# design.net
KiCad netlist of a schematic drawn in Altium Designer
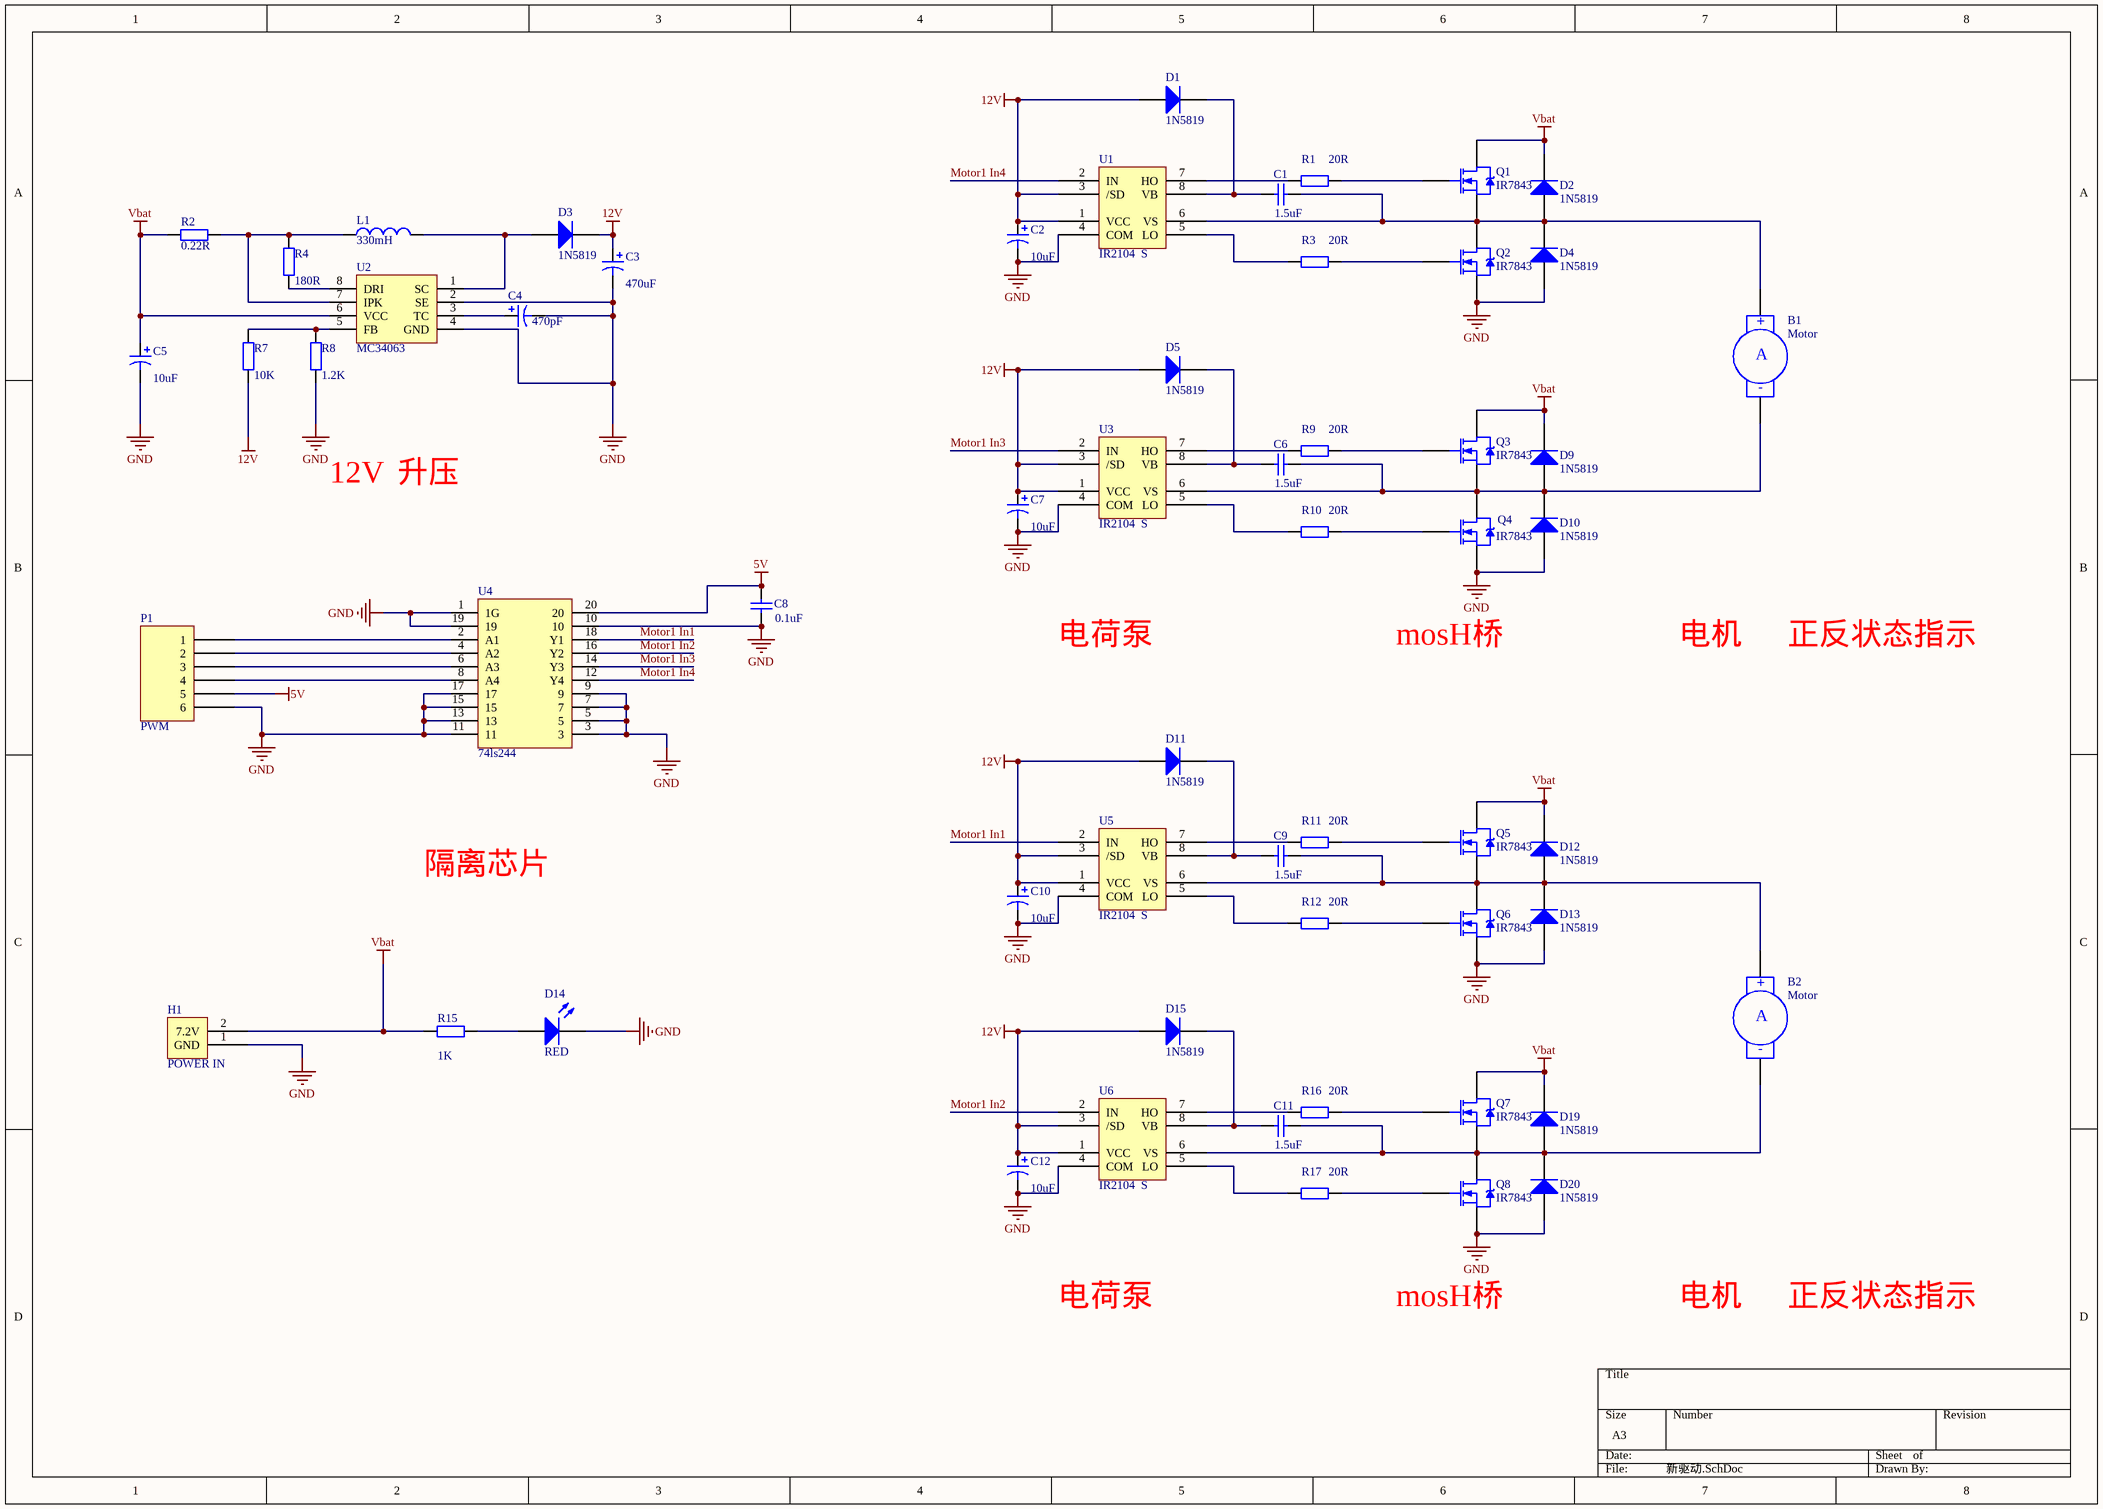
[diagram p0: 新驱动.SchDoc]

(export (version "E")
  (design (tool "Eeschema 10.0.6"))
  (components
    (comp (ref "B1")
      (value "Motor")
      (footprint "KF301-2P")
      (description "Servo Motor")
      (fields (field (name "PUBLISHER") "Altium Limited"))
      (libsource (lib "Miscellaneous Devices") (part "Motor Servo"))
    )
    (comp (ref "B2")
      (value "Motor")
      (footprint "KF301-2P")
      (description "Servo Motor")
      (fields (field (name "PUBLISHER") "Altium Limited"))
      (libsource (lib "Miscellaneous Devices") (part "Motor Servo"))
    )
    (comp (ref "C1")
      (value "1.5uF")
      (footprint "0805(2012)")
      (description "Capacitor")
      (fields (field (name "Comment") "Cap") (field (name "PUBLISHER") "Altium Limited"))
      (libsource (lib "Miscellaneous Devices") (part "Cap"))
    )
    (comp (ref "C2")
      (value "10uF")
      (footprint "SOD-323(0805)")
      (description "Polarized Capacitor (Radial)")
      (fields (field (name "Comment") "Cap Pol1") (field (name "PUBLISHER") "Altium Limited"))
      (libsource (lib "Miscellaneous Devices") (part "Cap Pol1"))
    )
    (comp (ref "C3")
      (value "470uF")
      (footprint "RB5-10.5")
      (description "Polarized Capacitor (Radial)")
      (fields (field (name "Comment") "Cap Pol1") (field (name "PUBLISHER") "Altium Limited"))
      (libsource (lib "Miscellaneous Devices") (part "Cap Pol1"))
    )
    (comp (ref "C4")
      (value "470pF")
      (footprint "SOD-323(0805)")
      (description "Polarized Capacitor (Radial)")
      (fields (field (name "Comment") "Cap Pol1") (field (name "PUBLISHER") "Altium Limited"))
      (libsource (lib "Miscellaneous Devices") (part "Cap Pol1"))
    )
    (comp (ref "C5")
      (value "10uF")
      (footprint "SOD-323(0805)")
      (description "Polarized Capacitor (Radial)")
      (fields (field (name "Comment") "Cap Pol1") (field (name "PUBLISHER") "Altium Limited"))
      (libsource (lib "Miscellaneous Devices") (part "Cap Pol1"))
    )
    (comp (ref "C6")
      (value "1.5uF")
      (footprint "0805(2012)")
      (description "Capacitor")
      (fields (field (name "Comment") "Cap") (field (name "PUBLISHER") "Altium Limited"))
      (libsource (lib "Miscellaneous Devices") (part "Cap"))
    )
    (comp (ref "C7")
      (value "10uF")
      (footprint "SOD-323(0805)")
      (description "Polarized Capacitor (Radial)")
      (fields (field (name "Comment") "Cap Pol1") (field (name "PUBLISHER") "Altium Limited"))
      (libsource (lib "Miscellaneous Devices") (part "Cap Pol1"))
    )
    (comp (ref "C8")
      (value "0.1uF")
      (footprint "0805(2012)")
      (description "Capacitor")
      (fields (field (name "Comment") "Cap") (field (name "PUBLISHER") "Altium Limited"))
      (libsource (lib "Miscellaneous Devices") (part "Cap"))
    )
    (comp (ref "C9")
      (value "1.5uF")
      (footprint "0805(2012)")
      (description "Capacitor")
      (fields (field (name "Comment") "Cap") (field (name "PUBLISHER") "Altium Limited"))
      (libsource (lib "Miscellaneous Devices") (part "Cap"))
    )
    (comp (ref "C10")
      (value "10uF")
      (footprint "SOD-323(0805)")
      (description "Polarized Capacitor (Radial)")
      (fields (field (name "Comment") "Cap Pol1") (field (name "PUBLISHER") "Altium Limited"))
      (libsource (lib "Miscellaneous Devices") (part "Cap Pol1"))
    )
    (comp (ref "C11")
      (value "1.5uF")
      (footprint "0805(2012)")
      (description "Capacitor")
      (fields (field (name "Comment") "Cap") (field (name "PUBLISHER") "Altium Limited"))
      (libsource (lib "Miscellaneous Devices") (part "Cap"))
    )
    (comp (ref "C12")
      (value "10uF")
      (footprint "SOD-323(0805)")
      (description "Polarized Capacitor (Radial)")
      (fields (field (name "Comment") "Cap Pol1") (field (name "PUBLISHER") "Altium Limited"))
      (libsource (lib "Miscellaneous Devices") (part "Cap Pol1"))
    )
    (comp (ref "D1")
      (value "1N5819")
      (footprint "0805(2012)")
      (description "Silicon Epitaxial Planar Diode for Various Detector, Modulator, Demodulator")
      (fields (field (name "PUBLISHER") "Altium Limited"))
      (libsource (lib "Renesas Diode") (part "1N4148"))
    )
    (comp (ref "D2")
      (value "1N5819")
      (footprint "0805(2012)")
      (description "Silicon Epitaxial Planar Diode for Various Detector, Modulator, Demodulator")
      (fields (field (name "PUBLISHER") "Altium Limited"))
      (libsource (lib "Renesas Diode") (part "1N4148"))
    )
    (comp (ref "D3")
      (value "1N5819")
      (footprint "0805(2012)")
      (description "Silicon Epitaxial Planar Diode for Various Detector, Modulator, Demodulator")
      (fields (field (name "PUBLISHER") "Altium Limited"))
      (libsource (lib "Renesas Diode") (part "1N4148"))
    )
    (comp (ref "D4")
      (value "1N5819")
      (footprint "0805(2012)")
      (description "Silicon Epitaxial Planar Diode for Various Detector, Modulator, Demodulator")
      (fields (field (name "PUBLISHER") "Altium Limited"))
      (libsource (lib "13th_motor") (part "1N4148"))
    )
    (comp (ref "D5")
      (value "1N5819")
      (footprint "0805(2012)")
      (description "Silicon Epitaxial Planar Diode for Various Detector, Modulator, Demodulator")
      (fields (field (name "PUBLISHER") "Altium Limited"))
      (libsource (lib "Renesas Diode") (part "1N4148"))
    )
    (comp (ref "D9")
      (value "1N5819")
      (footprint "0805(2012)")
      (description "Silicon Epitaxial Planar Diode for Various Detector, Modulator, Demodulator")
      (fields (field (name "PUBLISHER") "Altium Limited"))
      (libsource (lib "Renesas Diode") (part "1N4148"))
    )
    (comp (ref "D10")
      (value "1N5819")
      (footprint "0805(2012)")
      (description "Silicon Epitaxial Planar Diode for Various Detector, Modulator, Demodulator")
      (fields (field (name "PUBLISHER") "Altium Limited"))
      (libsource (lib "Renesas Diode") (part "1N4148"))
    )
    (comp (ref "D11")
      (value "1N5819")
      (footprint "0805(2012)")
      (description "Silicon Epitaxial Planar Diode for Various Detector, Modulator, Demodulator")
      (fields (field (name "PUBLISHER") "Altium Limited"))
      (libsource (lib "Renesas Diode") (part "1N4148"))
    )
    (comp (ref "D12")
      (value "1N5819")
      (footprint "0805(2012)")
      (description "Silicon Epitaxial Planar Diode for Various Detector, Modulator, Demodulator")
      (fields (field (name "PUBLISHER") "Altium Limited"))
      (libsource (lib "Renesas Diode") (part "1N4148"))
    )
    (comp (ref "D13")
      (value "1N5819")
      (footprint "0805(2012)")
      (description "Silicon Epitaxial Planar Diode for Various Detector, Modulator, Demodulator")
      (fields (field (name "PUBLISHER") "Altium Limited"))
      (libsource (lib "Renesas Diode") (part "1N4148"))
    )
    (comp (ref "D14")
      (value "RED")
      (footprint "0805LED")
      (description "Typical RED, GREEN, YELLOW, AMBER GaAs LED")
      (fields (field (name "PUBLISHER") "Altium Limited"))
      (libsource (lib "Miscellaneous Devices") (part "LED2"))
    )
    (comp (ref "D15")
      (value "1N5819")
      (footprint "0805(2012)")
      (description "Silicon Epitaxial Planar Diode for Various Detector, Modulator, Demodulator")
      (fields (field (name "PUBLISHER") "Altium Limited"))
      (libsource (lib "Renesas Diode") (part "1N4148"))
    )
    (comp (ref "D19")
      (value "1N5819")
      (footprint "0805(2012)")
      (description "Silicon Epitaxial Planar Diode for Various Detector, Modulator, Demodulator")
      (fields (field (name "PUBLISHER") "Altium Limited"))
      (libsource (lib "Renesas Diode") (part "1N4148"))
    )
    (comp (ref "D20")
      (value "1N5819")
      (footprint "0805(2012)")
      (description "Silicon Epitaxial Planar Diode for Various Detector, Modulator, Demodulator")
      (fields (field (name "PUBLISHER") "Altium Limited"))
      (libsource (lib "Renesas Diode") (part "1N4148"))
    )
    (comp (ref "H1")
      (value "POWER IN")
      (footprint "KF301-2P")
      (libsource (lib "MOS motor") (part "POWER IN"))
    )
    (comp (ref "L1")
      (value "330mH")
      (footprint "电感10*12")
      (description "Inductor")
      (fields (field (name "PUBLISHER") "Altium Limited"))
      (libsource (lib "Miscellaneous Devices") (part "Inductor"))
    )
    (comp (ref "P1") (value "PWM") (footprint "HDR1X6") (libsource (lib "MOS motor") (part "PWM")))
    (comp (ref "Q1")
      (value "IR7843")
      (footprint "LR7843")
      (description "N-Channel Power MOSFET")
      (fields (field (name "PUBLISHER") "Altium Limited"))
      (libsource (lib "PowerIn") (part "IR7843"))
    )
    (comp (ref "Q2")
      (value "IR7843")
      (footprint "LR7843")
      (description "N-Channel Power MOSFET")
      (fields (field (name "PUBLISHER") "Altium Limited"))
      (libsource (lib "PowerIn") (part "IR7843"))
    )
    (comp (ref "Q3")
      (value "IR7843")
      (footprint "LR7843")
      (description "N-Channel Power MOSFET")
      (fields (field (name "PUBLISHER") "Altium Limited"))
      (libsource (lib "PowerIn") (part "IR7843"))
    )
    (comp (ref "Q4")
      (value "IR7843")
      (footprint "LR7843")
      (description "N-Channel Power MOSFET")
      (fields (field (name "PUBLISHER") "Altium Limited"))
      (libsource (lib "PowerIn") (part "IR7843"))
    )
    (comp (ref "Q5")
      (value "IR7843")
      (footprint "LR7843")
      (description "N-Channel Power MOSFET")
      (fields (field (name "PUBLISHER") "Altium Limited"))
      (libsource (lib "PowerIn") (part "IR7843"))
    )
    (comp (ref "Q6")
      (value "IR7843")
      (footprint "LR7843")
      (description "N-Channel Power MOSFET")
      (fields (field (name "PUBLISHER") "Altium Limited"))
      (libsource (lib "PowerIn") (part "IR7843"))
    )
    (comp (ref "Q7")
      (value "IR7843")
      (footprint "LR7843")
      (description "N-Channel Power MOSFET")
      (fields (field (name "PUBLISHER") "Altium Limited"))
      (libsource (lib "PowerIn") (part "IR7843"))
    )
    (comp (ref "Q8")
      (value "IR7843")
      (footprint "LR7843")
      (description "N-Channel Power MOSFET")
      (fields (field (name "PUBLISHER") "Altium Limited"))
      (libsource (lib "PowerIn") (part "IR7843"))
    )
    (comp (ref "R1")
      (value "20R")
      (footprint "0805(2012)")
      (description "Resistor")
      (fields (field (name "Comment") "Res2") (field (name "PUBLISHER") "Altium Limited"))
      (libsource (lib "altium-import") (part "root_0_Res2_"))
    )
    (comp (ref "R2")
      (value "0.22R")
      (footprint "1206(3216)")
      (description "Resistor")
      (fields (field (name "Comment") "Res2") (field (name "PUBLISHER") "Altium Limited"))
      (libsource (lib "altium-import") (part "root_2_Res2_"))
    )
    (comp (ref "R3")
      (value "20R")
      (footprint "0805(2012)")
      (description "Resistor")
      (fields (field (name "Comment") "Res2") (field (name "PUBLISHER") "Altium Limited"))
      (libsource (lib "altium-import") (part "root_0_Res2_"))
    )
    (comp (ref "R4")
      (value "180R")
      (footprint "0805(2012)")
      (description "Resistor")
      (fields (field (name "Comment") "Res2") (field (name "PUBLISHER") "Altium Limited"))
      (libsource (lib "altium-import") (part "root_1_Res2_"))
    )
    (comp (ref "R7")
      (value "10K")
      (footprint "0805(2012)")
      (description "Resistor")
      (fields (field (name "Comment") "Res2") (field (name "PUBLISHER") "Altium Limited"))
      (libsource (lib "altium-import") (part "root_1_Res2_"))
    )
    (comp (ref "R8")
      (value "1.2K")
      (footprint "0805(2012)")
      (description "Resistor")
      (fields (field (name "Comment") "Res2") (field (name "PUBLISHER") "Altium Limited"))
      (libsource (lib "altium-import") (part "root_1_Res2_"))
    )
    (comp (ref "R9")
      (value "20R")
      (footprint "0805(2012)")
      (description "Resistor")
      (fields (field (name "Comment") "Res2") (field (name "PUBLISHER") "Altium Limited"))
      (libsource (lib "altium-import") (part "root_0_Res2_"))
    )
    (comp (ref "R10")
      (value "20R")
      (footprint "0805(2012)")
      (description "Resistor")
      (fields (field (name "Comment") "Res2") (field (name "PUBLISHER") "Altium Limited"))
      (libsource (lib "altium-import") (part "root_0_Res2_"))
    )
    (comp (ref "R11")
      (value "20R")
      (footprint "0805(2012)")
      (description "Resistor")
      (fields (field (name "Comment") "Res2") (field (name "PUBLISHER") "Altium Limited"))
      (libsource (lib "altium-import") (part "root_0_Res2_"))
    )
    (comp (ref "R12")
      (value "20R")
      (footprint "0805(2012)")
      (description "Resistor")
      (fields (field (name "Comment") "Res2") (field (name "PUBLISHER") "Altium Limited"))
      (libsource (lib "altium-import") (part "root_0_Res2_"))
    )
    (comp (ref "R15")
      (value "1K")
      (footprint "0805(2012)")
      (description "Resistor")
      (fields (field (name "Comment") "Res2") (field (name "PUBLISHER") "Altium Limited"))
      (libsource (lib "Miscellaneous Devices") (part "Res2"))
    )
    (comp (ref "R16")
      (value "20R")
      (footprint "0805(2012)")
      (description "Resistor")
      (fields (field (name "Comment") "Res2") (field (name "PUBLISHER") "Altium Limited"))
      (libsource (lib "altium-import") (part "root_0_Res2_"))
    )
    (comp (ref "R17")
      (value "20R")
      (footprint "0805(2012)")
      (description "Resistor")
      (fields (field (name "Comment") "Res2") (field (name "PUBLISHER") "Altium Limited"))
      (libsource (lib "altium-import") (part "root_0_Res2_"))
    )
    (comp (ref "U1") (value "IR2104  S") (footprint "IR2104S") (libsource (lib "IR2104S") (part "IR2104  S")))
    (comp (ref "U2") (value "MC34063") (footprint "MC34063") (libsource (lib "MC34063") (part "Component_1")))
    (comp (ref "U3") (value "IR2104  S") (footprint "IR2104S") (libsource (lib "IR2104S") (part "IR2104  S")))
    (comp (ref "U4") (value "74ls244") (footprint "74ls244Da") (libsource (lib "MOS motor") (part "74ls244")))
    (comp (ref "U5") (value "IR2104  S") (footprint "IR2104S") (libsource (lib "IR2104S") (part "IR2104  S")))
    (comp (ref "U6") (value "IR2104  S") (footprint "IR2104S") (libsource (lib "IR2104S") (part "IR2104  S")))
  )
  (nets
    (net (code "1") (name "/Motor1 In1") (class "Default")
      (node (ref "U4") (pin "18") (pinfunction "Y1_18") (pintype "passive"))
      (node (ref "U5") (pin "2") (pinfunction "IN_2") (pintype "passive"))
    )
    (net (code "2") (name "/Motor1 In2") (class "Default")
      (node (ref "U4") (pin "16") (pinfunction "Y2_16") (pintype "passive"))
      (node (ref "U6") (pin "2") (pinfunction "IN_2") (pintype "passive"))
    )
    (net (code "3") (name "/Motor1 In3") (class "Default")
      (node (ref "U3") (pin "2") (pinfunction "IN_2") (pintype "passive"))
      (node (ref "U4") (pin "14") (pinfunction "Y3_14") (pintype "passive"))
    )
    (net (code "4") (name "/Motor1 In4") (class "Default")
      (node (ref "U1") (pin "2") (pinfunction "IN_2") (pintype "passive"))
      (node (ref "U4") (pin "12") (pinfunction "Y4_12") (pintype "passive"))
    )
    (net (code "5") (name "5V") (class "Default")
      (node (ref "C8") (pin "2") (pinfunction "2_2") (pintype "passive"))
      (node (ref "P1") (pin "5") (pinfunction "5_5") (pintype "passive"))
      (node (ref "U4") (pin "20") (pinfunction "20_20") (pintype "passive"))
    )
    (net (code "6") (name "12V") (class "Default")
      (node (ref "C10") (pin "1") (pinfunction "1_1") (pintype "passive"))
      (node (ref "C12") (pin "1") (pinfunction "1_1") (pintype "passive"))
      (node (ref "C2") (pin "1") (pinfunction "1_1") (pintype "passive"))
      (node (ref "C3") (pin "1") (pinfunction "1_1") (pintype "passive"))
      (node (ref "C7") (pin "1") (pinfunction "1_1") (pintype "passive"))
      (node (ref "D1") (pin "2") (pinfunction "A_2") (pintype "passive"))
      (node (ref "D11") (pin "2") (pinfunction "A_2") (pintype "passive"))
      (node (ref "D15") (pin "2") (pinfunction "A_2") (pintype "passive"))
      (node (ref "D3") (pin "1") (pinfunction "K_1") (pintype "passive"))
      (node (ref "D5") (pin "2") (pinfunction "A_2") (pintype "passive"))
      (node (ref "R7") (pin "1") (pinfunction "1_1") (pintype "passive"))
      (node (ref "U1") (pin "1") (pinfunction "VCC_1") (pintype "passive"))
      (node (ref "U1") (pin "3") (pinfunction "/SD_3") (pintype "passive"))
      (node (ref "U3") (pin "1") (pinfunction "VCC_1") (pintype "passive"))
      (node (ref "U3") (pin "3") (pinfunction "/SD_3") (pintype "passive"))
      (node (ref "U5") (pin "1") (pinfunction "VCC_1") (pintype "passive"))
      (node (ref "U5") (pin "3") (pinfunction "/SD_3") (pintype "passive"))
      (node (ref "U6") (pin "1") (pinfunction "VCC_1") (pintype "passive"))
      (node (ref "U6") (pin "3") (pinfunction "/SD_3") (pintype "passive"))
    )
    (net (code "7") (name "GND") (class "Default")
      (node (ref "C10") (pin "2") (pinfunction "2_2") (pintype "passive"))
      (node (ref "C12") (pin "2") (pinfunction "2_2") (pintype "passive"))
      (node (ref "C2") (pin "2") (pinfunction "2_2") (pintype "passive"))
      (node (ref "C3") (pin "2") (pinfunction "2_2") (pintype "passive"))
      (node (ref "C4") (pin "2") (pinfunction "2_2") (pintype "passive"))
      (node (ref "C5") (pin "2") (pinfunction "2_2") (pintype "passive"))
      (node (ref "C7") (pin "2") (pinfunction "2_2") (pintype "passive"))
      (node (ref "C8") (pin "1") (pinfunction "1_1") (pintype "passive"))
      (node (ref "D10") (pin "2") (pinfunction "A_2") (pintype "passive"))
      (node (ref "D13") (pin "2") (pinfunction "A_2") (pintype "passive"))
      (node (ref "D14") (pin "2") (pinfunction "K_2") (pintype "passive"))
      (node (ref "D20") (pin "2") (pinfunction "A_2") (pintype "passive"))
      (node (ref "D4") (pin "2") (pinfunction "A_2") (pintype "passive"))
      (node (ref "H1") (pin "1") (pinfunction "GND_1") (pintype "passive"))
      (node (ref "P1") (pin "6") (pinfunction "6_6") (pintype "passive"))
      (node (ref "Q2") (pin "3") (pinfunction "S_3") (pintype "passive"))
      (node (ref "Q4") (pin "3") (pinfunction "S_3") (pintype "passive"))
      (node (ref "Q6") (pin "3") (pinfunction "S_3") (pintype "passive"))
      (node (ref "Q8") (pin "3") (pinfunction "S_3") (pintype "passive"))
      (node (ref "R8") (pin "1") (pinfunction "1_1") (pintype "passive"))
      (node (ref "U1") (pin "4") (pinfunction "COM_4") (pintype "passive"))
      (node (ref "U2") (pin "2") (pinfunction "SE_2") (pintype "passive"))
      (node (ref "U2") (pin "4") (pinfunction "GND_4") (pintype "passive"))
      (node (ref "U3") (pin "4") (pinfunction "COM_4") (pintype "passive"))
      (node (ref "U4") (pin "1") (pinfunction "1G_1") (pintype "passive"))
      (node (ref "U4") (pin "10") (pinfunction "10_10") (pintype "passive"))
      (node (ref "U4") (pin "11") (pinfunction "11_11") (pintype "passive"))
      (node (ref "U4") (pin "13") (pinfunction "13_13") (pintype "passive"))
      (node (ref "U4") (pin "15") (pinfunction "15_15") (pintype "passive"))
      (node (ref "U4") (pin "17") (pinfunction "17_17") (pintype "passive"))
      (node (ref "U4") (pin "19") (pinfunction "19_19") (pintype "passive"))
      (node (ref "U4") (pin "3") (pinfunction "3_3") (pintype "passive"))
      (node (ref "U4") (pin "5") (pinfunction "5_5") (pintype "passive"))
      (node (ref "U4") (pin "7") (pinfunction "7_7") (pintype "passive"))
      (node (ref "U4") (pin "9") (pinfunction "9_9") (pintype "passive"))
      (node (ref "U5") (pin "4") (pinfunction "COM_4") (pintype "passive"))
      (node (ref "U6") (pin "4") (pinfunction "COM_4") (pintype "passive"))
    )
    (net (code "8") (name "Net-(B1-+)") (class "Default")
      (node (ref "B1") (pin "1") (pinfunction "+_1") (pintype "passive"))
      (node (ref "C1") (pin "2") (pinfunction "2_2") (pintype "passive"))
      (node (ref "D2") (pin "2") (pinfunction "A_2") (pintype "passive"))
      (node (ref "D4") (pin "1") (pinfunction "K_1") (pintype "passive"))
      (node (ref "Q1") (pin "3") (pinfunction "S_3") (pintype "passive"))
      (node (ref "Q2") (pin "2") (pinfunction "D_2") (pintype "passive"))
      (node (ref "U1") (pin "6") (pinfunction "VS_6") (pintype "passive"))
    )
    (net (code "9") (name "Net-(B1--)") (class "Default")
      (node (ref "B1") (pin "2") (pinfunction "-_2") (pintype "passive"))
      (node (ref "C6") (pin "2") (pinfunction "2_2") (pintype "passive"))
      (node (ref "D10") (pin "1") (pinfunction "K_1") (pintype "passive"))
      (node (ref "D9") (pin "2") (pinfunction "A_2") (pintype "passive"))
      (node (ref "Q3") (pin "3") (pinfunction "S_3") (pintype "passive"))
      (node (ref "Q4") (pin "2") (pinfunction "D_2") (pintype "passive"))
      (node (ref "U3") (pin "6") (pinfunction "VS_6") (pintype "passive"))
    )
    (net (code "10") (name "Net-(B2-+)") (class "Default")
      (node (ref "B2") (pin "1") (pinfunction "+_1") (pintype "passive"))
      (node (ref "C9") (pin "2") (pinfunction "2_2") (pintype "passive"))
      (node (ref "D12") (pin "2") (pinfunction "A_2") (pintype "passive"))
      (node (ref "D13") (pin "1") (pinfunction "K_1") (pintype "passive"))
      (node (ref "Q5") (pin "3") (pinfunction "S_3") (pintype "passive"))
      (node (ref "Q6") (pin "2") (pinfunction "D_2") (pintype "passive"))
      (node (ref "U5") (pin "6") (pinfunction "VS_6") (pintype "passive"))
    )
    (net (code "11") (name "Net-(B2--)") (class "Default")
      (node (ref "B2") (pin "2") (pinfunction "-_2") (pintype "passive"))
      (node (ref "C11") (pin "2") (pinfunction "2_2") (pintype "passive"))
      (node (ref "D19") (pin "2") (pinfunction "A_2") (pintype "passive"))
      (node (ref "D20") (pin "1") (pinfunction "K_1") (pintype "passive"))
      (node (ref "Q7") (pin "3") (pinfunction "S_3") (pintype "passive"))
      (node (ref "Q8") (pin "2") (pinfunction "D_2") (pintype "passive"))
      (node (ref "U6") (pin "6") (pinfunction "VS_6") (pintype "passive"))
    )
    (net (code "12") (name "Net-(D1-K)") (class "Default")
      (node (ref "C1") (pin "1") (pinfunction "1_1") (pintype "passive"))
      (node (ref "D1") (pin "1") (pinfunction "K_1") (pintype "passive"))
      (node (ref "U1") (pin "8") (pinfunction "VB_8") (pintype "passive"))
    )
    (net (code "13") (name "Net-(D3-A)") (class "Default")
      (node (ref "D3") (pin "2") (pinfunction "A_2") (pintype "passive"))
      (node (ref "L1") (pin "2") (pinfunction "2_2") (pintype "passive"))
      (node (ref "U2") (pin "1") (pinfunction "SC_1") (pintype "passive"))
    )
    (net (code "14") (name "Net-(D5-K)") (class "Default")
      (node (ref "C6") (pin "1") (pinfunction "1_1") (pintype "passive"))
      (node (ref "D5") (pin "1") (pinfunction "K_1") (pintype "passive"))
      (node (ref "U3") (pin "8") (pinfunction "VB_8") (pintype "passive"))
    )
    (net (code "15") (name "Net-(D11-K)") (class "Default")
      (node (ref "C9") (pin "1") (pinfunction "1_1") (pintype "passive"))
      (node (ref "D11") (pin "1") (pinfunction "K_1") (pintype "passive"))
      (node (ref "U5") (pin "8") (pinfunction "VB_8") (pintype "passive"))
    )
    (net (code "16") (name "Net-(D14-A)") (class "Default")
      (node (ref "D14") (pin "1") (pinfunction "A_1") (pintype "passive"))
      (node (ref "R15") (pin "2") (pinfunction "2_2") (pintype "passive"))
    )
    (net (code "17") (name "Net-(D15-K)") (class "Default")
      (node (ref "C11") (pin "1") (pinfunction "1_1") (pintype "passive"))
      (node (ref "D15") (pin "1") (pinfunction "K_1") (pintype "passive"))
      (node (ref "U6") (pin "8") (pinfunction "VB_8") (pintype "passive"))
    )
    (net (code "18") (name "Net-(Q1-G)") (class "Default")
      (node (ref "Q1") (pin "1") (pinfunction "G_1") (pintype "passive"))
      (node (ref "R1") (pin "2") (pinfunction "2_2") (pintype "passive"))
    )
    (net (code "19") (name "Net-(Q2-G)") (class "Default")
      (node (ref "Q2") (pin "1") (pinfunction "G_1") (pintype "passive"))
      (node (ref "R3") (pin "2") (pinfunction "2_2") (pintype "passive"))
    )
    (net (code "20") (name "Net-(Q3-G)") (class "Default")
      (node (ref "Q3") (pin "1") (pinfunction "G_1") (pintype "passive"))
      (node (ref "R9") (pin "2") (pinfunction "2_2") (pintype "passive"))
    )
    (net (code "21") (name "Net-(Q4-G)") (class "Default")
      (node (ref "Q4") (pin "1") (pinfunction "G_1") (pintype "passive"))
      (node (ref "R10") (pin "2") (pinfunction "2_2") (pintype "passive"))
    )
    (net (code "22") (name "Net-(Q5-G)") (class "Default")
      (node (ref "Q5") (pin "1") (pinfunction "G_1") (pintype "passive"))
      (node (ref "R11") (pin "2") (pinfunction "2_2") (pintype "passive"))
    )
    (net (code "23") (name "Net-(Q6-G)") (class "Default")
      (node (ref "Q6") (pin "1") (pinfunction "G_1") (pintype "passive"))
      (node (ref "R12") (pin "2") (pinfunction "2_2") (pintype "passive"))
    )
    (net (code "24") (name "Net-(Q7-G)") (class "Default")
      (node (ref "Q7") (pin "1") (pinfunction "G_1") (pintype "passive"))
      (node (ref "R16") (pin "2") (pinfunction "2_2") (pintype "passive"))
    )
    (net (code "25") (name "Net-(Q8-G)") (class "Default")
      (node (ref "Q8") (pin "1") (pinfunction "G_1") (pintype "passive"))
      (node (ref "R17") (pin "2") (pinfunction "2_2") (pintype "passive"))
    )
    (net (code "26") (name "Net-(U1-HO)") (class "Default")
      (node (ref "R1") (pin "1") (pinfunction "1_1") (pintype "passive"))
      (node (ref "U1") (pin "7") (pinfunction "HO_7") (pintype "passive"))
    )
    (net (code "27") (name "Net-(U1-LO)") (class "Default")
      (node (ref "R3") (pin "1") (pinfunction "1_1") (pintype "passive"))
      (node (ref "U1") (pin "5") (pinfunction "LO_5") (pintype "passive"))
    )
    (net (code "28") (name "Net-(U2-DRI)") (class "Default")
      (node (ref "R4") (pin "1") (pinfunction "1_1") (pintype "passive"))
      (node (ref "U2") (pin "8") (pinfunction "DRI_8") (pintype "passive"))
    )
    (net (code "29") (name "Net-(U2-FB)") (class "Default")
      (node (ref "R7") (pin "2") (pinfunction "2_2") (pintype "passive"))
      (node (ref "R8") (pin "2") (pinfunction "2_2") (pintype "passive"))
      (node (ref "U2") (pin "5") (pinfunction "FB_5") (pintype "passive"))
    )
    (net (code "30") (name "Net-(U2-IPK)") (class "Default")
      (node (ref "L1") (pin "1") (pinfunction "1_1") (pintype "passive"))
      (node (ref "R2") (pin "1") (pinfunction "1_1") (pintype "passive"))
      (node (ref "R4") (pin "2") (pinfunction "2_2") (pintype "passive"))
      (node (ref "U2") (pin "7") (pinfunction "IPK_7") (pintype "passive"))
    )
    (net (code "31") (name "Net-(U2-TC)") (class "Default")
      (node (ref "C4") (pin "1") (pinfunction "1_1") (pintype "passive"))
      (node (ref "U2") (pin "3") (pinfunction "TC_3") (pintype "passive"))
    )
    (net (code "32") (name "Net-(U3-HO)") (class "Default")
      (node (ref "R9") (pin "1") (pinfunction "1_1") (pintype "passive"))
      (node (ref "U3") (pin "7") (pinfunction "HO_7") (pintype "passive"))
    )
    (net (code "33") (name "Net-(U3-LO)") (class "Default")
      (node (ref "R10") (pin "1") (pinfunction "1_1") (pintype "passive"))
      (node (ref "U3") (pin "5") (pinfunction "LO_5") (pintype "passive"))
    )
    (net (code "34") (name "Net-(U4-A1)") (class "Default")
      (node (ref "P1") (pin "1") (pinfunction "1_1") (pintype "passive"))
      (node (ref "U4") (pin "2") (pinfunction "A1_2") (pintype "passive"))
    )
    (net (code "35") (name "Net-(U4-A2)") (class "Default")
      (node (ref "P1") (pin "2") (pinfunction "2_2") (pintype "passive"))
      (node (ref "U4") (pin "4") (pinfunction "A2_4") (pintype "passive"))
    )
    (net (code "36") (name "Net-(U4-A3)") (class "Default")
      (node (ref "P1") (pin "3") (pinfunction "3_3") (pintype "passive"))
      (node (ref "U4") (pin "6") (pinfunction "A3_6") (pintype "passive"))
    )
    (net (code "37") (name "Net-(U4-A4)") (class "Default")
      (node (ref "P1") (pin "4") (pinfunction "4_4") (pintype "passive"))
      (node (ref "U4") (pin "8") (pinfunction "A4_8") (pintype "passive"))
    )
    (net (code "38") (name "Net-(U5-HO)") (class "Default")
      (node (ref "R11") (pin "1") (pinfunction "1_1") (pintype "passive"))
      (node (ref "U5") (pin "7") (pinfunction "HO_7") (pintype "passive"))
    )
    (net (code "39") (name "Net-(U5-LO)") (class "Default")
      (node (ref "R12") (pin "1") (pinfunction "1_1") (pintype "passive"))
      (node (ref "U5") (pin "5") (pinfunction "LO_5") (pintype "passive"))
    )
    (net (code "40") (name "Net-(U6-HO)") (class "Default")
      (node (ref "R16") (pin "1") (pinfunction "1_1") (pintype "passive"))
      (node (ref "U6") (pin "7") (pinfunction "HO_7") (pintype "passive"))
    )
    (net (code "41") (name "Net-(U6-LO)") (class "Default")
      (node (ref "R17") (pin "1") (pinfunction "1_1") (pintype "passive"))
      (node (ref "U6") (pin "5") (pinfunction "LO_5") (pintype "passive"))
    )
    (net (code "42") (name "Vbat") (class "Default")
      (node (ref "C5") (pin "1") (pinfunction "1_1") (pintype "passive"))
      (node (ref "D12") (pin "1") (pinfunction "K_1") (pintype "passive"))
      (node (ref "D19") (pin "1") (pinfunction "K_1") (pintype "passive"))
      (node (ref "D2") (pin "1") (pinfunction "K_1") (pintype "passive"))
      (node (ref "D9") (pin "1") (pinfunction "K_1") (pintype "passive"))
      (node (ref "H1") (pin "2") (pinfunction "7.2V_2") (pintype "passive"))
      (node (ref "Q1") (pin "2") (pinfunction "D_2") (pintype "passive"))
      (node (ref "Q3") (pin "2") (pinfunction "D_2") (pintype "passive"))
      (node (ref "Q5") (pin "2") (pinfunction "D_2") (pintype "passive"))
      (node (ref "Q7") (pin "2") (pinfunction "D_2") (pintype "passive"))
      (node (ref "R15") (pin "1") (pinfunction "1_1") (pintype "passive"))
      (node (ref "R2") (pin "2") (pinfunction "2_2") (pintype "passive"))
      (node (ref "U2") (pin "6") (pinfunction "VCC_6") (pintype "passive"))
    )
  )
)
